# SmartRock_EC.net
KiCad netlist of a schematic drawn in EAGLE
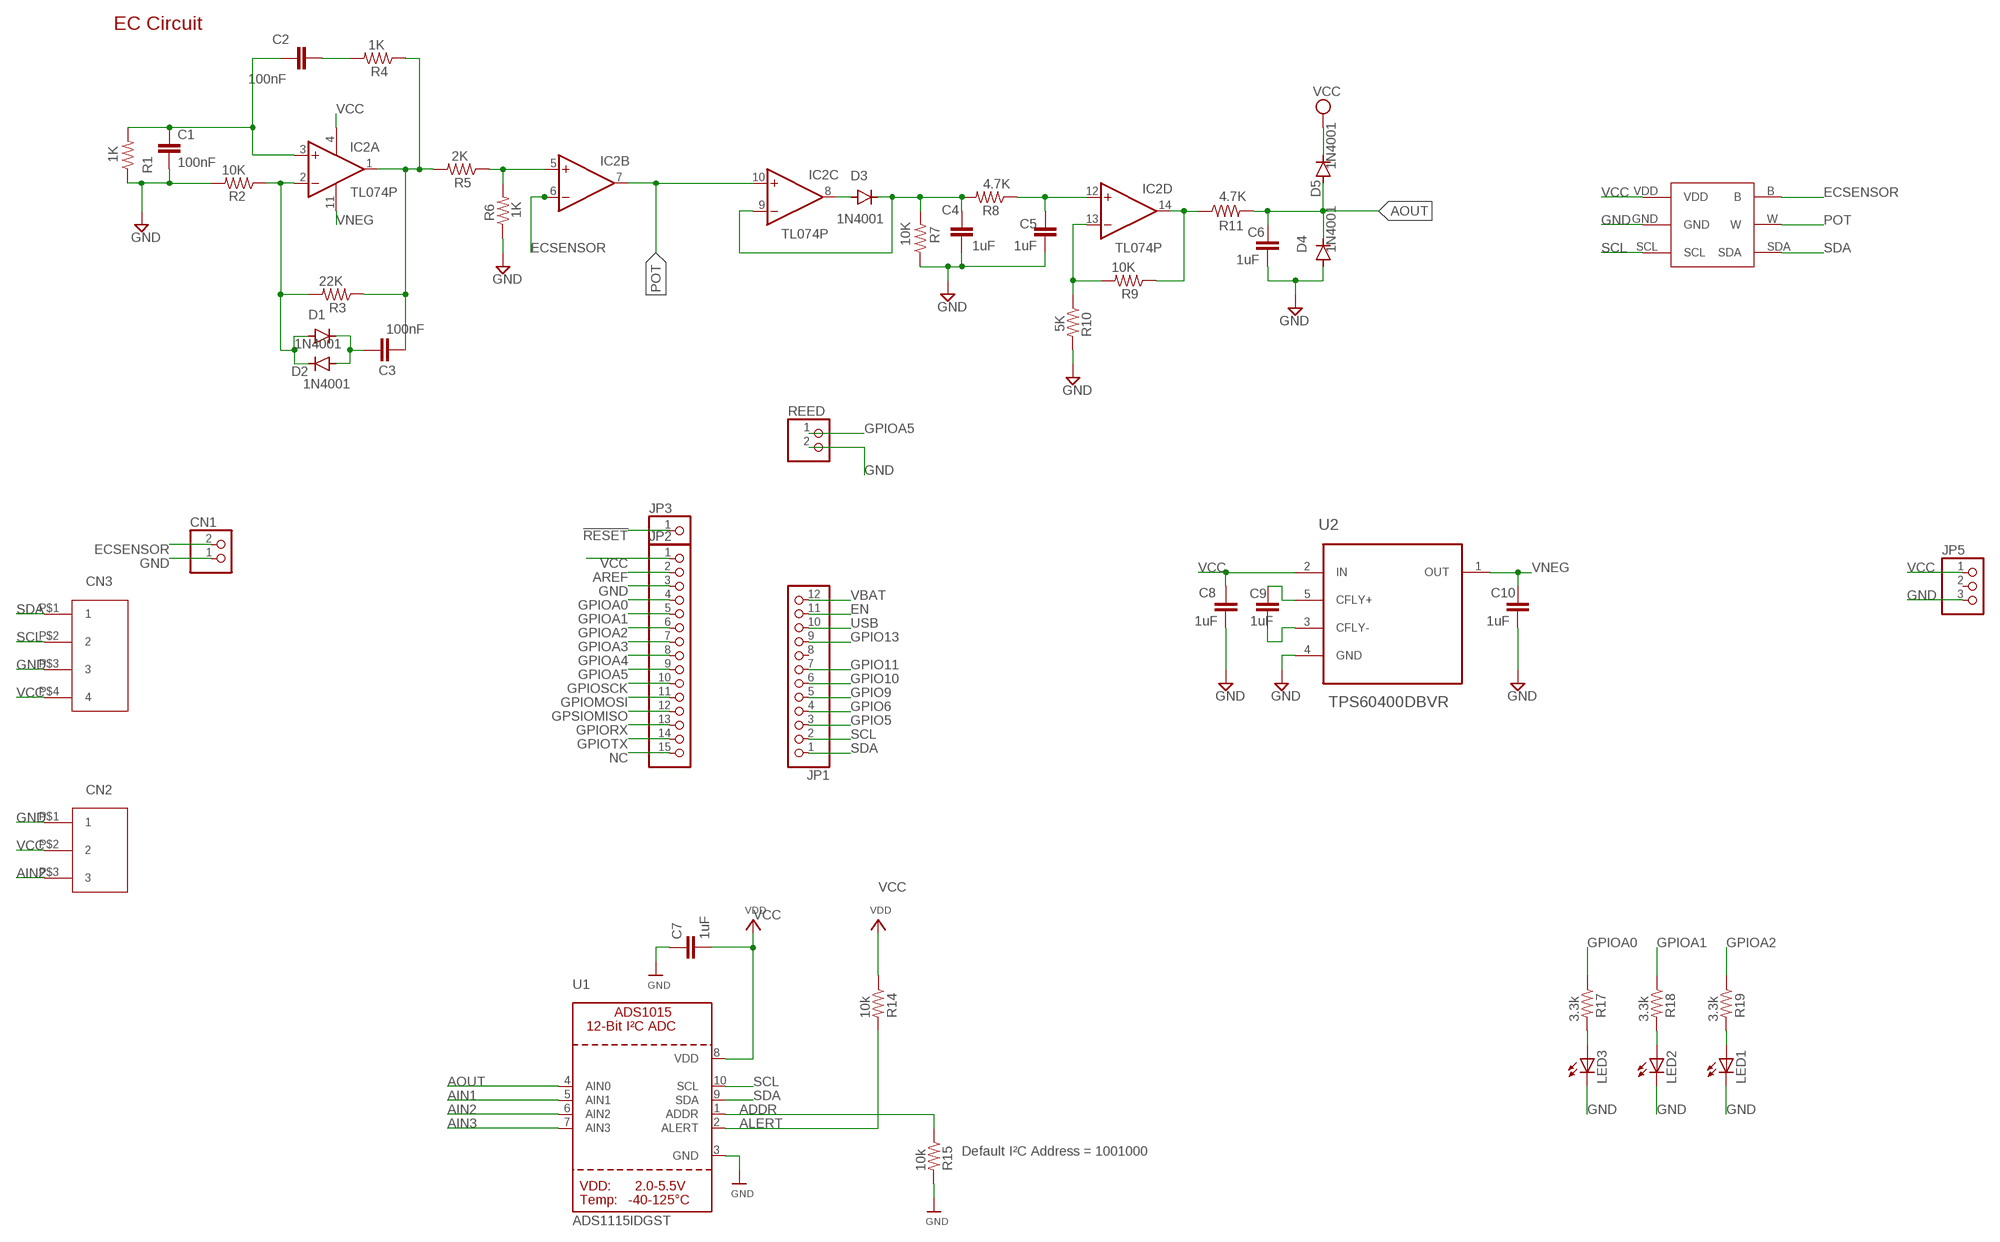
[diagram p0: schematic, sheet 1]

(export (version "E")
  (design (tool "Eeschema 10.0.6"))
  (components
    (comp (ref "C1")
      (value "100nF")
      (footprint "eagle-import:C1206")
      (libsource (lib "eagle-import") (part "C-EUC1206"))
    )
    (comp (ref "C2")
      (value "100nF")
      (footprint "eagle-import:C1206")
      (libsource (lib "eagle-import") (part "C-EUC1206"))
    )
    (comp (ref "C3")
      (value "100nF")
      (footprint "eagle-import:C1206")
      (libsource (lib "eagle-import") (part "C-EUC1206"))
    )
    (comp (ref "C4")
      (value "1uF")
      (footprint "eagle-import:C1206")
      (libsource (lib "eagle-import") (part "C-EUC1206"))
    )
    (comp (ref "C5")
      (value "1uF")
      (footprint "eagle-import:C1206")
      (libsource (lib "eagle-import") (part "C-EUC1206"))
    )
    (comp (ref "C6")
      (value "1uF")
      (footprint "eagle-import:C1206")
      (libsource (lib "eagle-import") (part "C-EUC1206"))
    )
    (comp (ref "C7")
      (value "1uF")
      (footprint "eagle-import:C1206")
      (libsource (lib "eagle-import") (part "C-EUC1206"))
    )
    (comp (ref "C8")
      (value "1uF")
      (footprint "eagle-import:C1206")
      (libsource (lib "eagle-import") (part "C-EUC1206"))
    )
    (comp (ref "C9")
      (value "1uF")
      (footprint "eagle-import:C1206")
      (libsource (lib "eagle-import") (part "C-EUC1206"))
    )
    (comp (ref "C10")
      (value "1uF")
      (footprint "eagle-import:C1206")
      (libsource (lib "eagle-import") (part "C-EUC1206"))
    )
    (comp (ref "CN1")
      (value "JST_2PIN-THM")
      (footprint "eagle-import:JST-PH-2-THM")
      (libsource (lib "eagle-import") (part "JST_2PIN-THM"))
    )
    (comp (ref "D1")
      (value "1N4001")
      (footprint "eagle-import:D-5")
      (libsource (lib "eagle-import") (part "DIODE-D-5"))
    )
    (comp (ref "D2")
      (value "1N4001")
      (footprint "eagle-import:D-5")
      (libsource (lib "eagle-import") (part "DIODE-D-5"))
    )
    (comp (ref "D3")
      (value "1N4001")
      (footprint "eagle-import:D-5")
      (libsource (lib "eagle-import") (part "DIODE-D-5"))
    )
    (comp (ref "D4")
      (value "1N4001")
      (footprint "eagle-import:D-5")
      (libsource (lib "eagle-import") (part "DIODE-D-5"))
    )
    (comp (ref "D5")
      (value "1N4001")
      (footprint "eagle-import:D-5")
      (libsource (lib "eagle-import") (part "DIODE-D-5"))
    )
    (comp (ref "IC2")
      (value "TL074P")
      (footprint "eagle-import:DIL14")
      (libsource (lib "eagle-import") (part "TL074P"))
    )
    (comp (ref "JP1")
      (value "PINHD-1X12-CB")
      (footprint "eagle-import:1X12-CB")
      (libsource (lib "eagle-import") (part "PINHD-1X12-CB"))
    )
    (comp (ref "JP2")
      (value "PINHD-1X15-CB")
      (footprint "eagle-import:1X15-CB")
      (libsource (lib "eagle-import") (part "PINHD-1X15-CB"))
    )
    (comp (ref "JP3")
      (value "PINHD-1X1CB")
      (footprint "eagle-import:1X01-CLEANBIG")
      (libsource (lib "eagle-import") (part "PINHD-1X1CB"))
    )
    (comp (ref "JP5")
      (value "PINHD-1X3CB")
      (footprint "eagle-import:1X03-CLEANBIG")
      (libsource (lib "eagle-import") (part "PINHD-1X3CB"))
    )
    (comp (ref "LED1")
      (value "LEDSMT1206")
      (footprint "eagle-import:1206")
      (libsource (lib "eagle-import") (part "LEDSMT1206"))
    )
    (comp (ref "LED2")
      (value "LEDSMT1206")
      (footprint "eagle-import:1206")
      (libsource (lib "eagle-import") (part "LEDSMT1206"))
    )
    (comp (ref "LED3")
      (value "LEDSMT1206")
      (footprint "eagle-import:1206")
      (libsource (lib "eagle-import") (part "LEDSMT1206"))
    )
    (comp (ref "R1")
      (value "1K")
      (footprint "eagle-import:R1206")
      (libsource (lib "eagle-import") (part "R-US_R1206"))
    )
    (comp (ref "R2")
      (value "10K")
      (footprint "eagle-import:R1206")
      (libsource (lib "eagle-import") (part "R-US_R1206"))
    )
    (comp (ref "R3")
      (value "22K")
      (footprint "eagle-import:R1206")
      (libsource (lib "eagle-import") (part "R-US_R1206"))
    )
    (comp (ref "R4")
      (value "1K")
      (footprint "eagle-import:R1206")
      (libsource (lib "eagle-import") (part "R-US_R1206"))
    )
    (comp (ref "R5")
      (value "2K")
      (footprint "eagle-import:R1206")
      (libsource (lib "eagle-import") (part "R-US_R1206"))
    )
    (comp (ref "R6")
      (value "1K")
      (footprint "eagle-import:R1206")
      (libsource (lib "eagle-import") (part "R-US_R1206"))
    )
    (comp (ref "R7")
      (value "10K")
      (footprint "eagle-import:R1206")
      (libsource (lib "eagle-import") (part "R-US_R1206"))
    )
    (comp (ref "R8")
      (value "4.7K")
      (footprint "eagle-import:R1206")
      (libsource (lib "eagle-import") (part "R-US_R1206"))
    )
    (comp (ref "R9")
      (value "10K")
      (footprint "eagle-import:R1206")
      (libsource (lib "eagle-import") (part "R-US_R1206"))
    )
    (comp (ref "R10")
      (value "5K")
      (footprint "eagle-import:R1206")
      (libsource (lib "eagle-import") (part "R-US_R1206"))
    )
    (comp (ref "R11")
      (value "4.7K")
      (footprint "eagle-import:R1206")
      (libsource (lib "eagle-import") (part "R-US_R1206"))
    )
    (comp (ref "R14")
      (value "10k")
      (footprint "eagle-import:R1206")
      (libsource (lib "eagle-import") (part "R-US_R1206"))
    )
    (comp (ref "R15")
      (value "10k")
      (footprint "eagle-import:R1206")
      (libsource (lib "eagle-import") (part "R-US_R1206"))
    )
    (comp (ref "R17")
      (value "3.3k")
      (footprint "eagle-import:R1206")
      (libsource (lib "eagle-import") (part "R-US_R1206"))
    )
    (comp (ref "R18")
      (value "3.3k")
      (footprint "eagle-import:R1206")
      (libsource (lib "eagle-import") (part "R-US_R1206"))
    )
    (comp (ref "R19")
      (value "3.3k")
      (footprint "eagle-import:R1206")
      (libsource (lib "eagle-import") (part "R-US_R1206"))
    )
    (comp (ref "REED")
      (value "PINHD-1X2")
      (footprint "eagle-import:1X02")
      (libsource (lib "eagle-import") (part "PINHD-1X2"))
    )
    (comp (ref "U$1")
      (value "AD5246")
      (footprint "eagle-import:AD5246")
      (libsource (lib "eagle-import") (part "AD5246"))
    )
    (comp (ref "U$7")
      (value "JST_4PIN_2MM")
      (footprint "eagle-import:JST_4PIN_2MM")
      (libsource (lib "eagle-import") (part "JST_4PIN_2MM"))
    )
    (comp (ref "U$9")
      (value "JST_3PIN_2MM")
      (footprint "eagle-import:JST_3PIN_2MM")
      (libsource (lib "eagle-import") (part "JST_3PIN_2MM"))
    )
    (comp (ref "U1")
      (value "ADS1115IDGST")
      (footprint "eagle-import:MSOP10")
      (libsource (lib "eagle-import") (part "ADC_ADS1015"))
    )
    (comp (ref "U2")
      (value "TPS60400DBVR")
      (footprint "eagle-import:SOT95P280X145-5N")
      (fields (field (name "MF") "Texas Instruments"))
      (libsource (lib "eagle-import") (part "TPS60400DBVR"))
    )
  )
  (nets
    (net (code "1") (name "/ADDR") (class "Default")
      (node (ref "R15") (pin "1") (pinfunction "1_1") (pintype "passive"))
      (node (ref "U1") (pin "1") (pinfunction "ADDR_1") (pintype "bidirectional"))
    )
    (net (code "2") (name "/AIN1") (class "Default")
      (node (ref "U1") (pin "5") (pinfunction "AIN1_5") (pintype "bidirectional"))
    )
    (net (code "3") (name "/AIN2") (class "Default")
      (node (ref "U$9") (pin "P$3") (pinfunction "3_P$3") (pintype "bidirectional"))
      (node (ref "U1") (pin "6") (pinfunction "AIN2_6") (pintype "bidirectional"))
    )
    (net (code "4") (name "/AIN3") (class "Default")
      (node (ref "U1") (pin "7") (pinfunction "AIN3_7") (pintype "bidirectional"))
    )
    (net (code "5") (name "/ALERT") (class "Default")
      (node (ref "R14") (pin "2") (pinfunction "2_2") (pintype "passive"))
      (node (ref "U1") (pin "2") (pinfunction "ALERT_2") (pintype "bidirectional"))
    )
    (net (code "6") (name "/AREF") (class "Default")
      (node (ref "JP2") (pin "2") (pinfunction "2_2") (pintype "passive"))
    )
    (net (code "7") (name "/ECSENSOR") (class "Default")
      (node (ref "CN1") (pin "2") (pinfunction "1_2") (pintype "passive"))
      (node (ref "IC2") (pin "6") (pinfunction "-IN_6") (pintype "input"))
      (node (ref "U$1") (pin "B") (pinfunction "B_B") (pintype "bidirectional"))
    )
    (net (code "8") (name "/EN") (class "Default")
      (node (ref "JP1") (pin "11") (pinfunction "11_11") (pintype "passive"))
    )
    (net (code "9") (name "/GPIO5") (class "Default")
      (node (ref "JP1") (pin "3") (pinfunction "3_3") (pintype "passive"))
    )
    (net (code "10") (name "/GPIO6") (class "Default")
      (node (ref "JP1") (pin "4") (pinfunction "4_4") (pintype "passive"))
    )
    (net (code "11") (name "/GPIO9") (class "Default")
      (node (ref "JP1") (pin "5") (pinfunction "5_5") (pintype "passive"))
    )
    (net (code "12") (name "/GPIO10") (class "Default")
      (node (ref "JP1") (pin "6") (pinfunction "6_6") (pintype "passive"))
    )
    (net (code "13") (name "/GPIO11") (class "Default")
      (node (ref "JP1") (pin "7") (pinfunction "7_7") (pintype "passive"))
    )
    (net (code "14") (name "/GPIO13") (class "Default")
      (node (ref "JP1") (pin "9") (pinfunction "9_9") (pintype "passive"))
    )
    (net (code "15") (name "/GPIOA0") (class "Default")
      (node (ref "JP2") (pin "4") (pinfunction "4_4") (pintype "passive"))
      (node (ref "R17") (pin "1") (pinfunction "1_1") (pintype "passive"))
    )
    (net (code "16") (name "/GPIOA1") (class "Default")
      (node (ref "JP2") (pin "5") (pinfunction "5_5") (pintype "passive"))
      (node (ref "R18") (pin "1") (pinfunction "1_1") (pintype "passive"))
    )
    (net (code "17") (name "/GPIOA2") (class "Default")
      (node (ref "JP2") (pin "6") (pinfunction "6_6") (pintype "passive"))
      (node (ref "R19") (pin "1") (pinfunction "1_1") (pintype "passive"))
    )
    (net (code "18") (name "/GPIOA3") (class "Default")
      (node (ref "JP2") (pin "7") (pinfunction "7_7") (pintype "passive"))
    )
    (net (code "19") (name "/GPIOA4") (class "Default")
      (node (ref "JP2") (pin "8") (pinfunction "8_8") (pintype "passive"))
    )
    (net (code "20") (name "/GPIOA5") (class "Default")
      (node (ref "JP2") (pin "9") (pinfunction "9_9") (pintype "passive"))
      (node (ref "REED") (pin "1") (pinfunction "1_1") (pintype "passive"))
    )
    (net (code "21") (name "/GPIOMOSI") (class "Default")
      (node (ref "JP2") (pin "11") (pinfunction "11_11") (pintype "passive"))
    )
    (net (code "22") (name "/GPIORX") (class "Default")
      (node (ref "JP2") (pin "13") (pinfunction "13_13") (pintype "passive"))
    )
    (net (code "23") (name "/GPIOSCK") (class "Default")
      (node (ref "JP2") (pin "10") (pinfunction "10_10") (pintype "passive"))
    )
    (net (code "24") (name "/GPIOTX") (class "Default")
      (node (ref "JP2") (pin "14") (pinfunction "14_14") (pintype "passive"))
    )
    (net (code "25") (name "/GPSIOMISO") (class "Default")
      (node (ref "JP2") (pin "12") (pinfunction "12_12") (pintype "passive"))
    )
    (net (code "26") (name "/NC") (class "Default")
      (node (ref "JP2") (pin "15") (pinfunction "15_15") (pintype "passive"))
    )
    (net (code "27") (name "/SCL") (class "Default")
      (node (ref "JP1") (pin "2") (pinfunction "2_2") (pintype "passive"))
      (node (ref "U$1") (pin "SCL") (pinfunction "SCL_SCL") (pintype "bidirectional"))
      (node (ref "U$7") (pin "P$2") (pinfunction "2_P$2") (pintype "bidirectional"))
      (node (ref "U1") (pin "10") (pinfunction "SCL_10") (pintype "bidirectional"))
    )
    (net (code "28") (name "/SDA") (class "Default")
      (node (ref "JP1") (pin "1") (pinfunction "1_1") (pintype "passive"))
      (node (ref "U$1") (pin "SDA") (pinfunction "SDA_SDA") (pintype "bidirectional"))
      (node (ref "U$7") (pin "P$1") (pinfunction "1_P$1") (pintype "bidirectional"))
      (node (ref "U1") (pin "9") (pinfunction "SDA_9") (pintype "bidirectional"))
    )
    (net (code "29") (name "/USB") (class "Default")
      (node (ref "JP1") (pin "10") (pinfunction "10_10") (pintype "passive"))
    )
    (net (code "30") (name "/VBAT") (class "Default")
      (node (ref "JP1") (pin "12") (pinfunction "12_12") (pintype "passive"))
    )
    (net (code "31") (name "/VNEG") (class "Default")
      (node (ref "C10") (pin "2") (pinfunction "2_2") (pintype "passive"))
      (node (ref "IC2") (pin "11") (pinfunction "V-_11") (pintype "power_in"))
      (node (ref "U2") (pin "1") (pinfunction "OUT_1") (pintype "output"))
    )
    (net (code "32") (name "/~{RESET}") (class "Default")
      (node (ref "JP3") (pin "1") (pinfunction "1_1") (pintype "passive"))
    )
    (net (code "33") (name "AOUT") (class "Default")
      (node (ref "C6") (pin "2") (pinfunction "2_2") (pintype "passive"))
      (node (ref "D4") (pin "C") (pinfunction "C_C") (pintype "passive"))
      (node (ref "D5") (pin "A") (pinfunction "A_A") (pintype "passive"))
      (node (ref "R11") (pin "2") (pinfunction "2_2") (pintype "passive"))
      (node (ref "U1") (pin "4") (pinfunction "AIN0_4") (pintype "bidirectional"))
    )
    (net (code "34") (name "GND") (class "Default")
      (node (ref "C1") (pin "2") (pinfunction "2_2") (pintype "passive"))
      (node (ref "C10") (pin "1") (pinfunction "1_1") (pintype "passive"))
      (node (ref "C4") (pin "1") (pinfunction "1_1") (pintype "passive"))
      (node (ref "C5") (pin "1") (pinfunction "1_1") (pintype "passive"))
      (node (ref "C6") (pin "1") (pinfunction "1_1") (pintype "passive"))
      (node (ref "C7") (pin "1") (pinfunction "1_1") (pintype "passive"))
      (node (ref "C8") (pin "1") (pinfunction "1_1") (pintype "passive"))
      (node (ref "CN1") (pin "1") (pinfunction "2_1") (pintype "passive"))
      (node (ref "D4") (pin "A") (pinfunction "A_A") (pintype "passive"))
      (node (ref "JP2") (pin "3") (pinfunction "3_3") (pintype "passive"))
      (node (ref "JP5") (pin "3") (pinfunction "3_3") (pintype "passive"))
      (node (ref "LED1") (pin "C") (pinfunction "C_C") (pintype "passive"))
      (node (ref "LED2") (pin "C") (pinfunction "C_C") (pintype "passive"))
      (node (ref "LED3") (pin "C") (pinfunction "C_C") (pintype "passive"))
      (node (ref "R1") (pin "1") (pinfunction "1_1") (pintype "passive"))
      (node (ref "R10") (pin "2") (pinfunction "2_2") (pintype "passive"))
      (node (ref "R15") (pin "2") (pinfunction "2_2") (pintype "passive"))
      (node (ref "R2") (pin "2") (pinfunction "2_2") (pintype "passive"))
      (node (ref "R6") (pin "1") (pinfunction "1_1") (pintype "passive"))
      (node (ref "R7") (pin "1") (pinfunction "1_1") (pintype "passive"))
      (node (ref "REED") (pin "2") (pinfunction "2_2") (pintype "passive"))
      (node (ref "U$1") (pin "GND") (pinfunction "GND_GND") (pintype "bidirectional"))
      (node (ref "U$7") (pin "P$3") (pinfunction "3_P$3") (pintype "bidirectional"))
      (node (ref "U$9") (pin "P$1") (pinfunction "1_P$1") (pintype "bidirectional"))
      (node (ref "U1") (pin "3") (pinfunction "GND_3") (pintype "bidirectional"))
      (node (ref "U2") (pin "4") (pinfunction "GND_4") (pintype "passive"))
    )
    (net (code "35") (name "Net-(C2-Pad2)") (class "Default")
      (node (ref "C2") (pin "2") (pinfunction "2_2") (pintype "passive"))
      (node (ref "R4") (pin "2") (pinfunction "2_2") (pintype "passive"))
    )
    (net (code "36") (name "Net-(C3-Pad1)") (class "Default")
      (node (ref "C3") (pin "1") (pinfunction "1_1") (pintype "passive"))
      (node (ref "D1") (pin "C") (pinfunction "C_C") (pintype "passive"))
      (node (ref "D2") (pin "A") (pinfunction "A_A") (pintype "passive"))
    )
    (net (code "37") (name "Net-(IC2A-+IN)") (class "Default")
      (node (ref "C1") (pin "1") (pinfunction "1_1") (pintype "passive"))
      (node (ref "C2") (pin "1") (pinfunction "1_1") (pintype "passive"))
      (node (ref "IC2") (pin "3") (pinfunction "+IN_3") (pintype "input"))
      (node (ref "R1") (pin "2") (pinfunction "2_2") (pintype "passive"))
    )
    (net (code "38") (name "Net-(IC2A--IN)") (class "Default")
      (node (ref "D1") (pin "A") (pinfunction "A_A") (pintype "passive"))
      (node (ref "D2") (pin "C") (pinfunction "C_C") (pintype "passive"))
      (node (ref "IC2") (pin "2") (pinfunction "-IN_2") (pintype "input"))
      (node (ref "R2") (pin "1") (pinfunction "1_1") (pintype "passive"))
      (node (ref "R3") (pin "2") (pinfunction "2_2") (pintype "passive"))
    )
    (net (code "39") (name "Net-(IC2A-OUT)") (class "Default")
      (node (ref "C3") (pin "2") (pinfunction "2_2") (pintype "passive"))
      (node (ref "IC2") (pin "1") (pinfunction "OUT_1") (pintype "output"))
      (node (ref "R3") (pin "1") (pinfunction "1_1") (pintype "passive"))
      (node (ref "R4") (pin "1") (pinfunction "1_1") (pintype "passive"))
      (node (ref "R5") (pin "2") (pinfunction "2_2") (pintype "passive"))
    )
    (net (code "40") (name "Net-(IC2B-+IN)") (class "Default")
      (node (ref "IC2") (pin "5") (pinfunction "+IN_5") (pintype "input"))
      (node (ref "R5") (pin "1") (pinfunction "1_1") (pintype "passive"))
      (node (ref "R6") (pin "2") (pinfunction "2_2") (pintype "passive"))
    )
    (net (code "41") (name "Net-(IC2C--IN)") (class "Default")
      (node (ref "C4") (pin "2") (pinfunction "2_2") (pintype "passive"))
      (node (ref "D3") (pin "C") (pinfunction "C_C") (pintype "passive"))
      (node (ref "IC2") (pin "9") (pinfunction "-IN_9") (pintype "input"))
      (node (ref "R7") (pin "2") (pinfunction "2_2") (pintype "passive"))
      (node (ref "R8") (pin "2") (pinfunction "2_2") (pintype "passive"))
    )
    (net (code "42") (name "Net-(IC2C-OUT)") (class "Default")
      (node (ref "D3") (pin "A") (pinfunction "A_A") (pintype "passive"))
      (node (ref "IC2") (pin "8") (pinfunction "OUT_8") (pintype "output"))
    )
    (net (code "43") (name "Net-(IC2D-+IN)") (class "Default")
      (node (ref "C5") (pin "2") (pinfunction "2_2") (pintype "passive"))
      (node (ref "IC2") (pin "12") (pinfunction "+IN_12") (pintype "input"))
      (node (ref "R8") (pin "1") (pinfunction "1_1") (pintype "passive"))
    )
    (net (code "44") (name "Net-(IC2D--IN)") (class "Default")
      (node (ref "IC2") (pin "13") (pinfunction "-IN_13") (pintype "input"))
      (node (ref "R10") (pin "1") (pinfunction "1_1") (pintype "passive"))
      (node (ref "R9") (pin "2") (pinfunction "2_2") (pintype "passive"))
    )
    (net (code "45") (name "Net-(IC2D-OUT)") (class "Default")
      (node (ref "IC2") (pin "14") (pinfunction "OUT_14") (pintype "output"))
      (node (ref "R11") (pin "1") (pinfunction "1_1") (pintype "passive"))
      (node (ref "R9") (pin "1") (pinfunction "1_1") (pintype "passive"))
    )
    (net (code "46") (name "Net-(LED1-PadA)") (class "Default")
      (node (ref "LED1") (pin "A") (pinfunction "A_A") (pintype "passive"))
      (node (ref "R19") (pin "2") (pinfunction "2_2") (pintype "passive"))
    )
    (net (code "47") (name "Net-(LED2-PadA)") (class "Default")
      (node (ref "LED2") (pin "A") (pinfunction "A_A") (pintype "passive"))
      (node (ref "R18") (pin "2") (pinfunction "2_2") (pintype "passive"))
    )
    (net (code "48") (name "Net-(LED3-PadA)") (class "Default")
      (node (ref "LED3") (pin "A") (pinfunction "A_A") (pintype "passive"))
      (node (ref "R17") (pin "2") (pinfunction "2_2") (pintype "passive"))
    )
    (net (code "49") (name "Net-(U2-CFLY+)") (class "Default")
      (node (ref "C9") (pin "2") (pinfunction "2_2") (pintype "passive"))
      (node (ref "U2") (pin "5") (pinfunction "CFLY+_5") (pintype "input"))
    )
    (net (code "50") (name "Net-(U2-CFLY-)") (class "Default")
      (node (ref "C9") (pin "1") (pinfunction "1_1") (pintype "passive"))
      (node (ref "U2") (pin "3") (pinfunction "CFLY-_3") (pintype "input"))
    )
    (net (code "51") (name "POT") (class "Default")
      (node (ref "IC2") (pin "10") (pinfunction "+IN_10") (pintype "input"))
      (node (ref "IC2") (pin "7") (pinfunction "OUT_7") (pintype "output"))
      (node (ref "U$1") (pin "W") (pinfunction "W_W") (pintype "bidirectional"))
    )
    (net (code "52") (name "VCC") (class "Default")
      (node (ref "C7") (pin "2") (pinfunction "2_2") (pintype "passive"))
      (node (ref "C8") (pin "2") (pinfunction "2_2") (pintype "passive"))
      (node (ref "D5") (pin "C") (pinfunction "C_C") (pintype "passive"))
      (node (ref "IC2") (pin "4") (pinfunction "V+_4") (pintype "power_in"))
      (node (ref "JP2") (pin "1") (pinfunction "1_1") (pintype "passive"))
      (node (ref "JP5") (pin "1") (pinfunction "1_1") (pintype "passive"))
      (node (ref "R14") (pin "1") (pinfunction "1_1") (pintype "passive"))
      (node (ref "U$1") (pin "VDD") (pinfunction "VDD_VDD") (pintype "bidirectional"))
      (node (ref "U$7") (pin "P$4") (pinfunction "4_P$4") (pintype "bidirectional"))
      (node (ref "U$9") (pin "P$2") (pinfunction "2_P$2") (pintype "bidirectional"))
      (node (ref "U1") (pin "8") (pinfunction "VDD_8") (pintype "bidirectional"))
      (node (ref "U2") (pin "2") (pinfunction "IN_2") (pintype "power_in"))
    )
    (net (code "53") (name "unconnected-(JP1-Pad8)") (class "Default")
      (node (ref "JP1") (pin "8") (pinfunction "8_8") (pintype "passive"))
    )
    (net (code "54") (name "unconnected-(JP5-Pad2)") (class "Default")
      (node (ref "JP5") (pin "2") (pinfunction "2_2") (pintype "passive"))
    )
  )
)
